# mainboard-mini.net
KiCad netlist of a schematic drawn in EAGLE
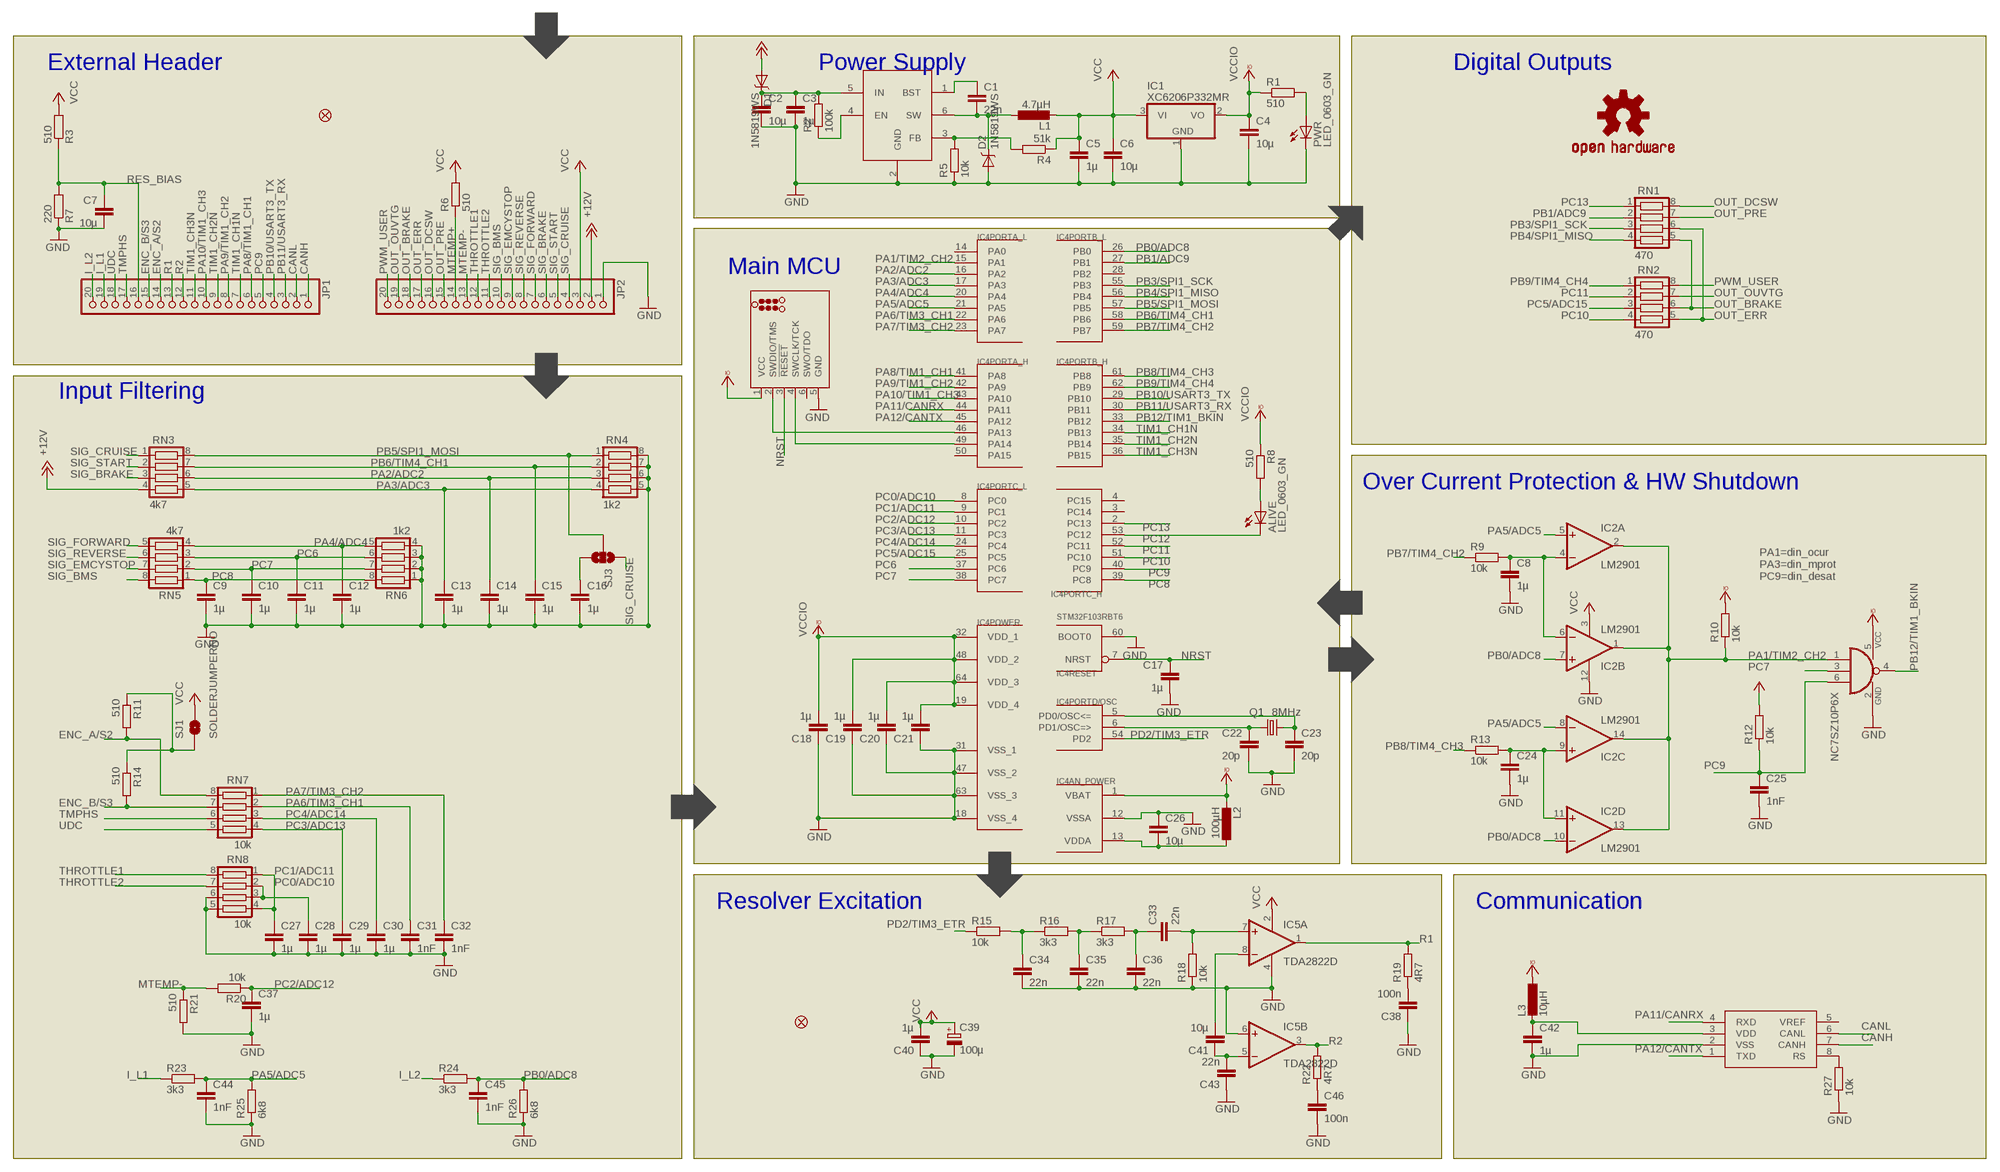
[diagram p0: schematic, sheet 1]

(export (version "E")
  (design (tool "Eeschema 10.0.6"))
  (components
    (comp (ref "ALIVE")
      (value "LED_0603_GN")
      (footprint "eagle-import:SML0805")
      (libsource (lib "eagle-import") (part "LEDSML0805"))
    )
    (comp (ref "C1")
      (value "22n")
      (footprint "eagle-import:C0603")
      (libsource (lib "eagle-import") (part "C-EUC0603"))
    )
    (comp (ref "C2")
      (value "10µ")
      (footprint "eagle-import:C0603")
      (libsource (lib "eagle-import") (part "C-EUC0603"))
    )
    (comp (ref "C3")
      (value "1µ")
      (footprint "eagle-import:C0603")
      (libsource (lib "eagle-import") (part "C-EUC0603"))
    )
    (comp (ref "C4")
      (value "10µ")
      (footprint "eagle-import:C0603")
      (libsource (lib "eagle-import") (part "C-EUC0603"))
    )
    (comp (ref "C5")
      (value "1µ")
      (footprint "eagle-import:C0603")
      (libsource (lib "eagle-import") (part "C-EUC0603"))
    )
    (comp (ref "C6")
      (value "10µ")
      (footprint "eagle-import:C0603")
      (libsource (lib "eagle-import") (part "C-EUC0603"))
    )
    (comp (ref "C7")
      (value "10µ")
      (footprint "eagle-import:C0603")
      (libsource (lib "eagle-import") (part "C-EUC0603"))
    )
    (comp (ref "C8")
      (value "1µ")
      (footprint "eagle-import:C0603")
      (libsource (lib "eagle-import") (part "C-EUC0603"))
    )
    (comp (ref "C9")
      (value "1µ")
      (footprint "eagle-import:C0603")
      (libsource (lib "eagle-import") (part "C-EUC0603"))
    )
    (comp (ref "C10")
      (value "1µ")
      (footprint "eagle-import:C0603")
      (libsource (lib "eagle-import") (part "C-EUC0603"))
    )
    (comp (ref "C11")
      (value "1µ")
      (footprint "eagle-import:C0603")
      (libsource (lib "eagle-import") (part "C-EUC0603"))
    )
    (comp (ref "C12")
      (value "1µ")
      (footprint "eagle-import:C0603")
      (libsource (lib "eagle-import") (part "C-EUC0603"))
    )
    (comp (ref "C13")
      (value "1µ")
      (footprint "eagle-import:C0603")
      (libsource (lib "eagle-import") (part "C-EUC0603"))
    )
    (comp (ref "C14")
      (value "1µ")
      (footprint "eagle-import:C0603")
      (libsource (lib "eagle-import") (part "C-EUC0603"))
    )
    (comp (ref "C15")
      (value "1µ")
      (footprint "eagle-import:C0603")
      (libsource (lib "eagle-import") (part "C-EUC0603"))
    )
    (comp (ref "C16")
      (value "1µ")
      (footprint "eagle-import:C0603")
      (libsource (lib "eagle-import") (part "C-EUC0603"))
    )
    (comp (ref "C17")
      (value "1µ")
      (footprint "eagle-import:C0603")
      (libsource (lib "eagle-import") (part "C-EUC0603"))
    )
    (comp (ref "C18")
      (value "1µ")
      (footprint "eagle-import:C0603")
      (libsource (lib "eagle-import") (part "C-EUC0603"))
    )
    (comp (ref "C19")
      (value "1µ")
      (footprint "eagle-import:C0603")
      (libsource (lib "eagle-import") (part "C-EUC0603"))
    )
    (comp (ref "C20")
      (value "1µ")
      (footprint "eagle-import:C0603")
      (libsource (lib "eagle-import") (part "C-EUC0603"))
    )
    (comp (ref "C21")
      (value "1µ")
      (footprint "eagle-import:C0603")
      (libsource (lib "eagle-import") (part "C-EUC0603"))
    )
    (comp (ref "C22")
      (value "20p")
      (footprint "eagle-import:C0603")
      (libsource (lib "eagle-import") (part "C-EUC0603"))
    )
    (comp (ref "C23")
      (value "20p")
      (footprint "eagle-import:C0603")
      (libsource (lib "eagle-import") (part "C-EUC0603"))
    )
    (comp (ref "C24")
      (value "1µ")
      (footprint "eagle-import:C0603")
      (libsource (lib "eagle-import") (part "C-EUC0603"))
    )
    (comp (ref "C25")
      (value "1nF")
      (footprint "eagle-import:C0603")
      (libsource (lib "eagle-import") (part "C-EUC0603"))
    )
    (comp (ref "C26")
      (value "10µ")
      (footprint "eagle-import:C0603")
      (libsource (lib "eagle-import") (part "C-EUC0603"))
    )
    (comp (ref "C27")
      (value "1µ")
      (footprint "eagle-import:C0603")
      (libsource (lib "eagle-import") (part "C-EUC0603"))
    )
    (comp (ref "C28")
      (value "1µ")
      (footprint "eagle-import:C0603")
      (libsource (lib "eagle-import") (part "C-EUC0603"))
    )
    (comp (ref "C29")
      (value "1µ")
      (footprint "eagle-import:C0603")
      (libsource (lib "eagle-import") (part "C-EUC0603"))
    )
    (comp (ref "C30")
      (value "1µ")
      (footprint "eagle-import:C0603")
      (libsource (lib "eagle-import") (part "C-EUC0603"))
    )
    (comp (ref "C31")
      (value "1nF")
      (footprint "eagle-import:C0603")
      (libsource (lib "eagle-import") (part "C-EUC0603"))
    )
    (comp (ref "C32")
      (value "1nF")
      (footprint "eagle-import:C0603")
      (libsource (lib "eagle-import") (part "C-EUC0603"))
    )
    (comp (ref "C33")
      (value "22n")
      (footprint "eagle-import:C0603")
      (libsource (lib "eagle-import") (part "C-EUC0603"))
    )
    (comp (ref "C34")
      (value "22n")
      (footprint "eagle-import:C0603")
      (libsource (lib "eagle-import") (part "C-EUC0603"))
    )
    (comp (ref "C35")
      (value "22n")
      (footprint "eagle-import:C0603")
      (libsource (lib "eagle-import") (part "C-EUC0603"))
    )
    (comp (ref "C36")
      (value "22n")
      (footprint "eagle-import:C0603")
      (libsource (lib "eagle-import") (part "C-EUC0603"))
    )
    (comp (ref "C37")
      (value "1µ")
      (footprint "eagle-import:C0603")
      (libsource (lib "eagle-import") (part "C-EUC0603"))
    )
    (comp (ref "C38")
      (value "100n")
      (footprint "eagle-import:C0603")
      (libsource (lib "eagle-import") (part "C-EUC0603"))
    )
    (comp (ref "C39")
      (value "100µ")
      (footprint "eagle-import:B_3528-21R")
      (libsource (lib "eagle-import") (part "CPOL-EUB/3528-21R"))
    )
    (comp (ref "C40")
      (value "1µ")
      (footprint "eagle-import:C0603")
      (libsource (lib "eagle-import") (part "C-EUC0603"))
    )
    (comp (ref "C41")
      (value "10µ")
      (footprint "eagle-import:C0603")
      (libsource (lib "eagle-import") (part "C-EUC0603"))
    )
    (comp (ref "C42")
      (value "1µ")
      (footprint "eagle-import:C0603")
      (libsource (lib "eagle-import") (part "C-EUC0603"))
    )
    (comp (ref "C43")
      (value "22n")
      (footprint "eagle-import:C0603")
      (libsource (lib "eagle-import") (part "C-EUC0603"))
    )
    (comp (ref "C44")
      (value "1nF")
      (footprint "eagle-import:C0603")
      (libsource (lib "eagle-import") (part "C-EUC0603"))
    )
    (comp (ref "C45")
      (value "1nF")
      (footprint "eagle-import:C0603")
      (libsource (lib "eagle-import") (part "C-EUC0603"))
    )
    (comp (ref "C46")
      (value "100n")
      (footprint "eagle-import:C0603")
      (libsource (lib "eagle-import") (part "C-EUC0603"))
    )
    (comp (ref "D1")
      (value "1N5819WS")
      (footprint "eagle-import:SOD-323")
      (libsource (lib "eagle-import") (part "BAT20JFILM"))
    )
    (comp (ref "D2")
      (value "1N5819WS")
      (footprint "eagle-import:SOD-323")
      (libsource (lib "eagle-import") (part "BAT20JFILM"))
    )
    (comp (ref "FID1")
      (value "FIDUCIAL1X2.5")
      (footprint "eagle-import:FIDUCIAL-1X2.5")
      (libsource (lib "eagle-import") (part "FIDUCIAL1X2.5"))
    )
    (comp (ref "FID2")
      (value "FIDUCIAL1X2.5")
      (footprint "eagle-import:FIDUCIAL-1X2.5")
      (libsource (lib "eagle-import") (part "FIDUCIAL1X2.5"))
    )
    (comp (ref "IC1")
      (value "XC6206P332MR")
      (footprint "eagle-import:SOT23")
      (libsource (lib "eagle-import") (part "MCP1703CB"))
    )
    (comp (ref "IC2")
      (value "LM2901")
      (footprint "eagle-import:SO14")
      (libsource (lib "eagle-import") (part "LM339D"))
    )
    (comp (ref "IC3")
      (value "NC7SZ10P6X")
      (footprint "eagle-import:SC70-6")
      (libsource (lib "eagle-import") (part "741G10X"))
    )
    (comp (ref "IC4")
      (value "STM32F103RBT6")
      (footprint "eagle-import:TQFP64")
      (libsource (lib "eagle-import") (part "STM32F10XRXT6"))
    )
    (comp (ref "IC5")
      (value "TDA2822D")
      (footprint "eagle-import:SO08")
      (libsource (lib "eagle-import") (part "TDA2822D"))
    )
    (comp (ref "IC6")
      (value "SN65HVD230")
      (footprint "eagle-import:SO08")
      (libsource (lib "eagle-import") (part "MCP2551"))
    )
    (comp (ref "IC7")
      (value "RT8259GE")
      (footprint "eagle-import:SOT23-6")
      (libsource (lib "eagle-import") (part "MB2359DJ"))
    )
    (comp (ref "J1")
      (value "TC2030_SWD-MCP")
      (footprint "eagle-import:TC2030-MCP")
      (libsource (lib "eagle-import") (part "TC2030_SWD-MCP"))
    )
    (comp (ref "JP1")
      (value "PINHD-1X20")
      (footprint "eagle-import:1X20")
      (libsource (lib "eagle-import") (part "PINHD-1X20"))
    )
    (comp (ref "JP2")
      (value "PINHD-1X20")
      (footprint "eagle-import:1X20")
      (libsource (lib "eagle-import") (part "PINHD-1X20"))
    )
    (comp (ref "L1")
      (value "4.7µH")
      (footprint "eagle-import:L2825P")
      (libsource (lib "eagle-import") (part "L-EUL2825P"))
    )
    (comp (ref "L2")
      (value "100µH")
      (footprint "eagle-import:L2012C")
      (libsource (lib "eagle-import") (part "L-EUL2012C"))
    )
    (comp (ref "L3")
      (value "10µH")
      (footprint "eagle-import:L2012C")
      (libsource (lib "eagle-import") (part "L-EUL2012C"))
    )
    (comp (ref "LOGO1")
      (value "OSHW-LOGOM")
      (footprint "eagle-import:OSHW-LOGO-M")
      (libsource (lib "eagle-import") (part "OSHW-LOGOM"))
    )
    (comp (ref "PWR")
      (value "LED_0603_GN")
      (footprint "eagle-import:SML0805")
      (libsource (lib "eagle-import") (part "LEDSML0805"))
    )
    (comp (ref "Q1")
      (value "8MHz")
      (footprint "eagle-import:CRYSTAL-TXC-7A")
      (libsource (lib "eagle-import") (part "CRYSTALTXC-7A"))
    )
    (comp (ref "R1")
      (value "510")
      (footprint "eagle-import:R0603")
      (libsource (lib "eagle-import") (part "R-EU_R0603"))
    )
    (comp (ref "R2")
      (value "100k")
      (footprint "eagle-import:R0603")
      (libsource (lib "eagle-import") (part "R-EU_R0603"))
    )
    (comp (ref "R3")
      (value "510")
      (footprint "eagle-import:R0603")
      (libsource (lib "eagle-import") (part "R-EU_R0603"))
    )
    (comp (ref "R4")
      (value "51k")
      (footprint "eagle-import:R0603")
      (libsource (lib "eagle-import") (part "R-EU_R0603"))
    )
    (comp (ref "R5")
      (value "10k")
      (footprint "eagle-import:R0603")
      (libsource (lib "eagle-import") (part "R-EU_R0603"))
    )
    (comp (ref "R6")
      (value "510")
      (footprint "eagle-import:R0603")
      (libsource (lib "eagle-import") (part "R-EU_R0603"))
    )
    (comp (ref "R7")
      (value "220")
      (footprint "eagle-import:R0603")
      (libsource (lib "eagle-import") (part "R-EU_R0603"))
    )
    (comp (ref "R8")
      (value "510")
      (footprint "eagle-import:R0603")
      (libsource (lib "eagle-import") (part "R-EU_R0603"))
    )
    (comp (ref "R9")
      (value "10k")
      (footprint "eagle-import:R0603")
      (libsource (lib "eagle-import") (part "R-EU_R0603"))
    )
    (comp (ref "R10")
      (value "10k")
      (footprint "eagle-import:R0603")
      (libsource (lib "eagle-import") (part "R-EU_R0603"))
    )
    (comp (ref "R11")
      (value "510")
      (footprint "eagle-import:R0603")
      (libsource (lib "eagle-import") (part "R-EU_R0603"))
    )
    (comp (ref "R12")
      (value "10k")
      (footprint "eagle-import:R0603")
      (libsource (lib "eagle-import") (part "R-EU_R0603"))
    )
    (comp (ref "R13")
      (value "10k")
      (footprint "eagle-import:R0603")
      (libsource (lib "eagle-import") (part "R-EU_R0603"))
    )
    (comp (ref "R14")
      (value "510")
      (footprint "eagle-import:R0603")
      (libsource (lib "eagle-import") (part "R-EU_R0603"))
    )
    (comp (ref "R15")
      (value "10k")
      (footprint "eagle-import:R0603")
      (libsource (lib "eagle-import") (part "R-EU_R0603"))
    )
    (comp (ref "R16")
      (value "3k3")
      (footprint "eagle-import:R0603")
      (libsource (lib "eagle-import") (part "R-EU_R0603"))
    )
    (comp (ref "R17")
      (value "3k3")
      (footprint "eagle-import:R0603")
      (libsource (lib "eagle-import") (part "R-EU_R0603"))
    )
    (comp (ref "R18")
      (value "10k")
      (footprint "eagle-import:R0603")
      (libsource (lib "eagle-import") (part "R-EU_R0603"))
    )
    (comp (ref "R19")
      (value "4R7")
      (footprint "eagle-import:R0603")
      (libsource (lib "eagle-import") (part "R-EU_R0603"))
    )
    (comp (ref "R20")
      (value "10k")
      (footprint "eagle-import:R0603")
      (libsource (lib "eagle-import") (part "R-EU_R0603"))
    )
    (comp (ref "R21")
      (value "510")
      (footprint "eagle-import:R0603")
      (libsource (lib "eagle-import") (part "R-EU_R0603"))
    )
    (comp (ref "R22")
      (value "4R7")
      (footprint "eagle-import:R0603")
      (libsource (lib "eagle-import") (part "R-EU_R0603"))
    )
    (comp (ref "R23")
      (value "3k3")
      (footprint "eagle-import:R0603")
      (libsource (lib "eagle-import") (part "R-EU_R0603"))
    )
    (comp (ref "R24")
      (value "3k3")
      (footprint "eagle-import:R0603")
      (libsource (lib "eagle-import") (part "R-EU_R0603"))
    )
    (comp (ref "R25")
      (value "6k8")
      (footprint "eagle-import:R0603")
      (libsource (lib "eagle-import") (part "R-EU_R0603"))
    )
    (comp (ref "R26")
      (value "6k8")
      (footprint "eagle-import:R0603")
      (libsource (lib "eagle-import") (part "R-EU_R0603"))
    )
    (comp (ref "R27")
      (value "10k")
      (footprint "eagle-import:R0603")
      (libsource (lib "eagle-import") (part "R-EU_R0603"))
    )
    (comp (ref "RN1")
      (value "470")
      (footprint "eagle-import:CTS742C083")
      (libsource (lib "eagle-import") (part "CTS742C083"))
    )
    (comp (ref "RN2")
      (value "470")
      (footprint "eagle-import:CTS742C083")
      (libsource (lib "eagle-import") (part "CTS742C083"))
    )
    (comp (ref "RN3")
      (value "4k7")
      (footprint "eagle-import:CTS742C083")
      (libsource (lib "eagle-import") (part "CTS742C083"))
    )
    (comp (ref "RN4")
      (value "1k2")
      (footprint "eagle-import:CTS742C083")
      (libsource (lib "eagle-import") (part "CTS742C083"))
    )
    (comp (ref "RN5")
      (value "4k7")
      (footprint "eagle-import:CTS742C083")
      (libsource (lib "eagle-import") (part "CTS742C083"))
    )
    (comp (ref "RN6")
      (value "1k2")
      (footprint "eagle-import:CTS742C083")
      (libsource (lib "eagle-import") (part "CTS742C083"))
    )
    (comp (ref "RN7")
      (value "10k")
      (footprint "eagle-import:CTS742C083")
      (libsource (lib "eagle-import") (part "CTS742C083"))
    )
    (comp (ref "RN8")
      (value "10k")
      (footprint "eagle-import:CTS742C083")
      (libsource (lib "eagle-import") (part "CTS742C083"))
    )
    (comp (ref "SJ1")
      (value "SOLDERJUMPERNO")
      (footprint "eagle-import:SJ_2S-NO")
      (libsource (lib "eagle-import") (part "SOLDERJUMPERNO"))
    )
    (comp (ref "SJ3")
      (value "SOLDERJUMPER_2WAYPASTE2&3")
      (footprint "eagle-import:SJ_3_PASTE2&3")
      (libsource (lib "eagle-import") (part "SOLDERJUMPER_2WAYPASTE2&3"))
    )
  )
  (nets
    (net (code "1") (name "+12V") (class "Default")
      (node (ref "D1") (pin "2") (pinfunction "A_2") (pintype "passive"))
      (node (ref "JP2") (pin "2") (pinfunction "2_2") (pintype "passive"))
      (node (ref "RN3") (pin "4") (pinfunction "4_4") (pintype "passive"))
    )
    (net (code "2") (name "/CANH") (class "Default")
      (node (ref "IC6") (pin "7") (pinfunction "CANH_7") (pintype "bidirectional"))
      (node (ref "JP1") (pin "1") (pinfunction "1_1") (pintype "passive"))
    )
    (net (code "3") (name "/CANL") (class "Default")
      (node (ref "IC6") (pin "6") (pinfunction "CANL_6") (pintype "bidirectional"))
      (node (ref "JP1") (pin "2") (pinfunction "2_2") (pintype "passive"))
    )
    (net (code "4") (name "/ENC_A{slash}S2") (class "Default")
      (node (ref "JP1") (pin "14") (pinfunction "14_14") (pintype "passive"))
      (node (ref "R11") (pin "2") (pinfunction "2_2") (pintype "passive"))
      (node (ref "RN7") (pin "8") (pinfunction "8_8") (pintype "passive"))
    )
    (net (code "5") (name "/ENC_B{slash}S3") (class "Default")
      (node (ref "JP1") (pin "15") (pinfunction "15_15") (pintype "passive"))
      (node (ref "R14") (pin "2") (pinfunction "2_2") (pintype "passive"))
      (node (ref "RN7") (pin "7") (pinfunction "7_7") (pintype "passive"))
    )
    (net (code "6") (name "/I_L1") (class "Default")
      (node (ref "JP1") (pin "19") (pinfunction "19_19") (pintype "passive"))
      (node (ref "R23") (pin "1") (pinfunction "1_1") (pintype "passive"))
    )
    (net (code "7") (name "/I_L2") (class "Default")
      (node (ref "JP1") (pin "20") (pinfunction "20_20") (pintype "passive"))
      (node (ref "R24") (pin "1") (pinfunction "1_1") (pintype "passive"))
    )
    (net (code "8") (name "/MTEMP+") (class "Default")
      (node (ref "JP2") (pin "14") (pinfunction "14_14") (pintype "passive"))
      (node (ref "R6") (pin "1") (pinfunction "1_1") (pintype "passive"))
    )
    (net (code "9") (name "/MTEMP-") (class "Default")
      (node (ref "JP2") (pin "13") (pinfunction "13_13") (pintype "passive"))
      (node (ref "R20") (pin "2") (pinfunction "2_2") (pintype "passive"))
      (node (ref "R21") (pin "1") (pinfunction "1_1") (pintype "passive"))
    )
    (net (code "10") (name "/NRST") (class "Default")
      (node (ref "C17") (pin "1") (pinfunction "1_1") (pintype "passive"))
      (node (ref "IC4") (pin "7") (pinfunction "NRST_7") (pintype "input"))
      (node (ref "J1") (pin "3") (pinfunction "~{RESET}_3") (pintype "output"))
    )
    (net (code "11") (name "/OUT_BRAKE") (class "Default")
      (node (ref "JP2") (pin "18") (pinfunction "18_18") (pintype "passive"))
      (node (ref "RN1") (pin "5") (pinfunction "5_5") (pintype "passive"))
      (node (ref "RN2") (pin "6") (pinfunction "6_6") (pintype "passive"))
    )
    (net (code "12") (name "/OUT_DCSW") (class "Default")
      (node (ref "JP2") (pin "16") (pinfunction "16_16") (pintype "passive"))
      (node (ref "RN1") (pin "8") (pinfunction "8_8") (pintype "passive"))
    )
    (net (code "13") (name "/OUT_ERR") (class "Default")
      (node (ref "JP2") (pin "17") (pinfunction "17_17") (pintype "passive"))
      (node (ref "RN1") (pin "6") (pinfunction "6_6") (pintype "passive"))
      (node (ref "RN2") (pin "5") (pinfunction "5_5") (pintype "passive"))
    )
    (net (code "14") (name "/OUT_OUVTG") (class "Default")
      (node (ref "JP2") (pin "19") (pinfunction "19_19") (pintype "passive"))
      (node (ref "RN2") (pin "7") (pinfunction "7_7") (pintype "passive"))
    )
    (net (code "15") (name "/OUT_PRE") (class "Default")
      (node (ref "JP2") (pin "15") (pinfunction "15_15") (pintype "passive"))
      (node (ref "RN1") (pin "7") (pinfunction "7_7") (pintype "passive"))
    )
    (net (code "16") (name "/PA1{slash}TIM2_CH2") (class "Default")
      (node (ref "IC2") (pin "1") (pinfunction "OUT_1") (pintype "open_collector"))
      (node (ref "IC2") (pin "13") (pinfunction "OUT_13") (pintype "open_collector"))
      (node (ref "IC2") (pin "14") (pinfunction "OUT_14") (pintype "open_collector"))
      (node (ref "IC2") (pin "2") (pinfunction "OUT_2") (pintype "open_collector"))
      (node (ref "IC3") (pin "1") (pinfunction "I0_1") (pintype "input"))
      (node (ref "IC4") (pin "15") (pinfunction "PA1_15") (pintype "bidirectional"))
      (node (ref "R10") (pin "1") (pinfunction "1_1") (pintype "passive"))
    )
    (net (code "17") (name "/PA2{slash}ADC2") (class "Default")
      (node (ref "C14") (pin "1") (pinfunction "1_1") (pintype "passive"))
      (node (ref "IC4") (pin "16") (pinfunction "PA2_16") (pintype "bidirectional"))
      (node (ref "RN3") (pin "6") (pinfunction "6_6") (pintype "passive"))
      (node (ref "RN4") (pin "3") (pinfunction "3_3") (pintype "passive"))
    )
    (net (code "18") (name "/PA3{slash}ADC3") (class "Default")
      (node (ref "C13") (pin "1") (pinfunction "1_1") (pintype "passive"))
      (node (ref "IC4") (pin "17") (pinfunction "PA3_17") (pintype "bidirectional"))
      (node (ref "RN3") (pin "5") (pinfunction "5_5") (pintype "passive"))
      (node (ref "RN4") (pin "4") (pinfunction "4_4") (pintype "passive"))
    )
    (net (code "19") (name "/PA4{slash}ADC4") (class "Default")
      (node (ref "C12") (pin "1") (pinfunction "1_1") (pintype "passive"))
      (node (ref "IC4") (pin "20") (pinfunction "PA4_20") (pintype "bidirectional"))
      (node (ref "RN5") (pin "4") (pinfunction "4_4") (pintype "passive"))
      (node (ref "RN6") (pin "5") (pinfunction "5_5") (pintype "passive"))
    )
    (net (code "20") (name "/PA5{slash}ADC5") (class "Default")
      (node (ref "C44") (pin "1") (pinfunction "1_1") (pintype "passive"))
      (node (ref "IC2") (pin "5") (pinfunction "+IN_5") (pintype "input"))
      (node (ref "IC2") (pin "8") (pinfunction "-IN_8") (pintype "input"))
      (node (ref "IC4") (pin "21") (pinfunction "PA5_21") (pintype "bidirectional"))
      (node (ref "R23") (pin "2") (pinfunction "2_2") (pintype "passive"))
      (node (ref "R25") (pin "2") (pinfunction "2_2") (pintype "passive"))
    )
    (net (code "21") (name "/PA6{slash}TIM3_CH1") (class "Default")
      (node (ref "C31") (pin "1") (pinfunction "1_1") (pintype "passive"))
      (node (ref "IC4") (pin "22") (pinfunction "PA6_22") (pintype "bidirectional"))
      (node (ref "RN7") (pin "2") (pinfunction "2_2") (pintype "passive"))
    )
    (net (code "22") (name "/PA7{slash}TIM3_CH2") (class "Default")
      (node (ref "C32") (pin "1") (pinfunction "1_1") (pintype "passive"))
      (node (ref "IC4") (pin "23") (pinfunction "PA7_23") (pintype "bidirectional"))
      (node (ref "RN7") (pin "1") (pinfunction "1_1") (pintype "passive"))
    )
    (net (code "23") (name "/PA8{slash}TIM1_CH1") (class "Default")
      (node (ref "IC4") (pin "41") (pinfunction "PA8_41") (pintype "bidirectional"))
      (node (ref "JP1") (pin "6") (pinfunction "6_6") (pintype "passive"))
    )
    (net (code "24") (name "/PA9{slash}TIM1_CH2") (class "Default")
      (node (ref "IC4") (pin "42") (pinfunction "PA9_42") (pintype "bidirectional"))
      (node (ref "JP1") (pin "8") (pinfunction "8_8") (pintype "passive"))
    )
    (net (code "25") (name "/PA10{slash}TIM1_CH3") (class "Default")
      (node (ref "IC4") (pin "43") (pinfunction "PA10_43") (pintype "bidirectional"))
      (node (ref "JP1") (pin "10") (pinfunction "10_10") (pintype "passive"))
    )
    (net (code "26") (name "/PA11{slash}CANRX") (class "Default")
      (node (ref "IC4") (pin "44") (pinfunction "PA11_44") (pintype "bidirectional"))
      (node (ref "IC6") (pin "4") (pinfunction "RXD_4") (pintype "bidirectional"))
    )
    (net (code "27") (name "/PA12{slash}CANTX") (class "Default")
      (node (ref "IC4") (pin "45") (pinfunction "PA12_45") (pintype "bidirectional"))
      (node (ref "IC6") (pin "1") (pinfunction "TXD_1") (pintype "bidirectional"))
    )
    (net (code "28") (name "/PB0{slash}ADC8") (class "Default")
      (node (ref "C45") (pin "1") (pinfunction "1_1") (pintype "passive"))
      (node (ref "IC2") (pin "10") (pinfunction "-IN_10") (pintype "input"))
      (node (ref "IC2") (pin "7") (pinfunction "+IN_7") (pintype "input"))
      (node (ref "IC4") (pin "26") (pinfunction "PB0_26") (pintype "bidirectional"))
      (node (ref "R24") (pin "2") (pinfunction "2_2") (pintype "passive"))
      (node (ref "R26") (pin "2") (pinfunction "2_2") (pintype "passive"))
    )
    (net (code "29") (name "/PB1{slash}ADC9") (class "Default")
      (node (ref "IC4") (pin "27") (pinfunction "PB1_27") (pintype "bidirectional"))
      (node (ref "RN1") (pin "2") (pinfunction "2_2") (pintype "passive"))
    )
    (net (code "30") (name "/PB3{slash}SPI1_SCK") (class "Default")
      (node (ref "IC4") (pin "55") (pinfunction "PB3_55") (pintype "bidirectional"))
      (node (ref "RN1") (pin "3") (pinfunction "3_3") (pintype "passive"))
    )
    (net (code "31") (name "/PB4{slash}SPI1_MISO") (class "Default")
      (node (ref "IC4") (pin "56") (pinfunction "PB4_56") (pintype "bidirectional"))
      (node (ref "RN1") (pin "4") (pinfunction "4_4") (pintype "passive"))
    )
    (net (code "32") (name "/PB5{slash}SPI1_MOSI") (class "Default")
      (node (ref "IC4") (pin "57") (pinfunction "PB5_57") (pintype "bidirectional"))
      (node (ref "RN3") (pin "8") (pinfunction "8_8") (pintype "passive"))
      (node (ref "RN4") (pin "1") (pinfunction "1_1") (pintype "passive"))
      (node (ref "SJ3") (pin "2") (pinfunction "2_2") (pintype "passive"))
    )
    (net (code "33") (name "/PB6{slash}TIM4_CH1") (class "Default")
      (node (ref "C15") (pin "1") (pinfunction "1_1") (pintype "passive"))
      (node (ref "IC4") (pin "58") (pinfunction "PB6_58") (pintype "bidirectional"))
      (node (ref "RN3") (pin "7") (pinfunction "7_7") (pintype "passive"))
      (node (ref "RN4") (pin "2") (pinfunction "2_2") (pintype "passive"))
    )
    (net (code "34") (name "/PB7{slash}TIM4_CH2") (class "Default")
      (node (ref "IC4") (pin "59") (pinfunction "PB7_59") (pintype "bidirectional"))
      (node (ref "R9") (pin "1") (pinfunction "1_1") (pintype "passive"))
    )
    (net (code "35") (name "/PB8{slash}TIM4_CH3") (class "Default")
      (node (ref "IC4") (pin "61") (pinfunction "PB8_61") (pintype "bidirectional"))
      (node (ref "R13") (pin "1") (pinfunction "1_1") (pintype "passive"))
    )
    (net (code "36") (name "/PB9{slash}TIM4_CH4") (class "Default")
      (node (ref "IC4") (pin "62") (pinfunction "PB9_62") (pintype "bidirectional"))
      (node (ref "RN2") (pin "1") (pinfunction "1_1") (pintype "passive"))
    )
    (net (code "37") (name "/PB10{slash}USART3_TX") (class "Default")
      (node (ref "IC4") (pin "29") (pinfunction "PB10_29") (pintype "bidirectional"))
      (node (ref "JP1") (pin "4") (pinfunction "4_4") (pintype "passive"))
    )
    (net (code "38") (name "/PB11{slash}USART3_RX") (class "Default")
      (node (ref "IC4") (pin "30") (pinfunction "PB11_30") (pintype "bidirectional"))
      (node (ref "JP1") (pin "3") (pinfunction "3_3") (pintype "passive"))
    )
    (net (code "39") (name "/PB12{slash}TIM1_BKIN") (class "Default")
      (node (ref "IC3") (pin "4") (pinfunction "O_4") (pintype "open_collector"))
      (node (ref "IC4") (pin "33") (pinfunction "PB12_33") (pintype "bidirectional"))
    )
    (net (code "40") (name "/PC0{slash}ADC10") (class "Default")
      (node (ref "C28") (pin "1") (pinfunction "1_1") (pintype "passive"))
      (node (ref "IC4") (pin "8") (pinfunction "PC0_8") (pintype "bidirectional"))
      (node (ref "RN8") (pin "2") (pinfunction "2_2") (pintype "passive"))
      (node (ref "RN8") (pin "3") (pinfunction "3_3") (pintype "passive"))
    )
    (net (code "41") (name "/PC1{slash}ADC11") (class "Default")
      (node (ref "C27") (pin "1") (pinfunction "1_1") (pintype "passive"))
      (node (ref "IC4") (pin "9") (pinfunction "PC1_9") (pintype "bidirectional"))
      (node (ref "RN8") (pin "1") (pinfunction "1_1") (pintype "passive"))
      (node (ref "RN8") (pin "4") (pinfunction "4_4") (pintype "passive"))
    )
    (net (code "42") (name "/PC2{slash}ADC12") (class "Default")
      (node (ref "C37") (pin "1") (pinfunction "1_1") (pintype "passive"))
      (node (ref "IC4") (pin "10") (pinfunction "PC2_10") (pintype "bidirectional"))
      (node (ref "R20") (pin "1") (pinfunction "1_1") (pintype "passive"))
    )
    (net (code "43") (name "/PC3{slash}ADC13") (class "Default")
      (node (ref "C29") (pin "1") (pinfunction "1_1") (pintype "passive"))
      (node (ref "IC4") (pin "11") (pinfunction "PC3_11") (pintype "bidirectional"))
      (node (ref "RN7") (pin "4") (pinfunction "4_4") (pintype "passive"))
    )
    (net (code "44") (name "/PC4{slash}ADC14") (class "Default")
      (node (ref "C30") (pin "1") (pinfunction "1_1") (pintype "passive"))
      (node (ref "IC4") (pin "24") (pinfunction "PC4_24") (pintype "bidirectional"))
      (node (ref "RN7") (pin "3") (pinfunction "3_3") (pintype "passive"))
    )
    (net (code "45") (name "/PC5{slash}ADC15") (class "Default")
      (node (ref "IC4") (pin "25") (pinfunction "PC5_25") (pintype "bidirectional"))
      (node (ref "RN2") (pin "3") (pinfunction "3_3") (pintype "passive"))
    )
    (net (code "46") (name "/PC6") (class "Default")
      (node (ref "C11") (pin "1") (pinfunction "1_1") (pintype "passive"))
      (node (ref "IC4") (pin "37") (pinfunction "PC6_37") (pintype "bidirectional"))
      (node (ref "RN5") (pin "3") (pinfunction "3_3") (pintype "passive"))
      (node (ref "RN6") (pin "6") (pinfunction "6_6") (pintype "passive"))
    )
    (net (code "47") (name "/PC7") (class "Default")
      (node (ref "C10") (pin "1") (pinfunction "1_1") (pintype "passive"))
      (node (ref "IC3") (pin "3") (pinfunction "I1_3") (pintype "input"))
      (node (ref "IC4") (pin "38") (pinfunction "PC7_38") (pintype "bidirectional"))
      (node (ref "RN5") (pin "2") (pinfunction "2_2") (pintype "passive"))
      (node (ref "RN6") (pin "7") (pinfunction "7_7") (pintype "passive"))
    )
    (net (code "48") (name "/PC8") (class "Default")
      (node (ref "C9") (pin "1") (pinfunction "1_1") (pintype "passive"))
      (node (ref "IC4") (pin "39") (pinfunction "PC8_39") (pintype "bidirectional"))
      (node (ref "RN5") (pin "1") (pinfunction "1_1") (pintype "passive"))
      (node (ref "RN6") (pin "8") (pinfunction "8_8") (pintype "passive"))
    )
    (net (code "49") (name "/PC9") (class "Default")
      (node (ref "C25") (pin "1") (pinfunction "1_1") (pintype "passive"))
      (node (ref "IC3") (pin "6") (pinfunction "I2_6") (pintype "input"))
      (node (ref "IC4") (pin "40") (pinfunction "PC9_40") (pintype "bidirectional"))
      (node (ref "JP1") (pin "5") (pinfunction "5_5") (pintype "passive"))
      (node (ref "R12") (pin "1") (pinfunction "1_1") (pintype "passive"))
    )
    (net (code "50") (name "/PC10") (class "Default")
      (node (ref "IC4") (pin "51") (pinfunction "PC10_51") (pintype "bidirectional"))
      (node (ref "RN2") (pin "4") (pinfunction "4_4") (pintype "passive"))
    )
    (net (code "51") (name "/PC11") (class "Default")
      (node (ref "IC4") (pin "52") (pinfunction "PC11_52") (pintype "bidirectional"))
      (node (ref "RN2") (pin "2") (pinfunction "2_2") (pintype "passive"))
    )
    (net (code "52") (name "/PC12") (class "Default")
      (node (ref "ALIVE") (pin "C") (pinfunction "C_C") (pintype "passive"))
      (node (ref "IC4") (pin "53") (pinfunction "PC12_53") (pintype "bidirectional"))
    )
    (net (code "53") (name "/PC13") (class "Default")
      (node (ref "IC4") (pin "2") (pinfunction "PC13_2") (pintype "bidirectional"))
      (node (ref "RN1") (pin "1") (pinfunction "1_1") (pintype "passive"))
    )
    (net (code "54") (name "/PD2{slash}TIM3_ETR") (class "Default")
      (node (ref "IC4") (pin "54") (pinfunction "PD2_54") (pintype "bidirectional"))
      (node (ref "R15") (pin "1") (pinfunction "1_1") (pintype "passive"))
    )
    (net (code "55") (name "/PWM_USER") (class "Default")
      (node (ref "JP2") (pin "20") (pinfunction "20_20") (pintype "passive"))
      (node (ref "RN2") (pin "8") (pinfunction "8_8") (pintype "passive"))
    )
    (net (code "56") (name "/R1") (class "Default")
      (node (ref "IC5") (pin "1") (pinfunction "OUT_1") (pintype "output"))
      (node (ref "JP1") (pin "13") (pinfunction "13_13") (pintype "passive"))
      (node (ref "R19") (pin "2") (pinfunction "2_2") (pintype "passive"))
    )
    (net (code "57") (name "/R2") (class "Default")
      (node (ref "IC5") (pin "3") (pinfunction "OUT_3") (pintype "output"))
      (node (ref "JP1") (pin "12") (pinfunction "12_12") (pintype "passive"))
      (node (ref "R22") (pin "2") (pinfunction "2_2") (pintype "passive"))
    )
    (net (code "58") (name "/RES_BIAS") (class "Default")
      (node (ref "C7") (pin "1") (pinfunction "1_1") (pintype "passive"))
      (node (ref "JP1") (pin "16") (pinfunction "16_16") (pintype "passive"))
      (node (ref "R3") (pin "1") (pinfunction "1_1") (pintype "passive"))
      (node (ref "R7") (pin "2") (pinfunction "2_2") (pintype "passive"))
    )
    (net (code "59") (name "/SIG_BMS") (class "Default")
      (node (ref "JP2") (pin "10") (pinfunction "10_10") (pintype "passive"))
      (node (ref "RN5") (pin "8") (pinfunction "8_8") (pintype "passive"))
    )
    (net (code "60") (name "/SIG_BRAKE") (class "Default")
      (node (ref "JP2") (pin "6") (pinfunction "6_6") (pintype "passive"))
      (node (ref "RN3") (pin "3") (pinfunction "3_3") (pintype "passive"))
    )
    (net (code "61") (name "/SIG_CRUISE") (class "Default")
      (node (ref "JP2") (pin "4") (pinfunction "4_4") (pintype "passive"))
      (node (ref "RN3") (pin "1") (pinfunction "1_1") (pintype "passive"))
      (node (ref "SJ3") (pin "1") (pinfunction "1_1") (pintype "passive"))
    )
    (net (code "62") (name "/SIG_EMCYSTOP") (class "Default")
      (node (ref "JP2") (pin "9") (pinfunction "9_9") (pintype "passive"))
      (node (ref "RN5") (pin "7") (pinfunction "7_7") (pintype "passive"))
    )
    (net (code "63") (name "/SIG_FORWARD") (class "Default")
      (node (ref "JP2") (pin "7") (pinfunction "7_7") (pintype "passive"))
      (node (ref "RN5") (pin "5") (pinfunction "5_5") (pintype "passive"))
    )
    (net (code "64") (name "/SIG_REVERSE") (class "Default")
      (node (ref "JP2") (pin "8") (pinfunction "8_8") (pintype "passive"))
      (node (ref "RN5") (pin "6") (pinfunction "6_6") (pintype "passive"))
    )
    (net (code "65") (name "/SIG_START") (class "Default")
      (node (ref "JP2") (pin "5") (pinfunction "5_5") (pintype "passive"))
      (node (ref "RN3") (pin "2") (pinfunction "2_2") (pintype "passive"))
    )
    (net (code "66") (name "/THROTTLE1") (class "Default")
      (node (ref "JP2") (pin "12") (pinfunction "12_12") (pintype "passive"))
      (node (ref "RN8") (pin "8") (pinfunction "8_8") (pintype "passive"))
    )
    (net (code "67") (name "/THROTTLE2") (class "Default")
      (node (ref "JP2") (pin "11") (pinfunction "11_11") (pintype "passive"))
      (node (ref "RN8") (pin "7") (pinfunction "7_7") (pintype "passive"))
    )
    (net (code "68") (name "/TIM1_CH1N") (class "Default")
      (node (ref "IC4") (pin "34") (pinfunction "PB13_34") (pintype "bidirectional"))
      (node (ref "JP1") (pin "7") (pinfunction "7_7") (pintype "passive"))
    )
    (net (code "69") (name "/TIM1_CH2N") (class "Default")
      (node (ref "IC4") (pin "35") (pinfunction "PB14_35") (pintype "bidirectional"))
      (node (ref "JP1") (pin "9") (pinfunction "9_9") (pintype "passive"))
    )
    (net (code "70") (name "/TIM1_CH3N") (class "Default")
      (node (ref "IC4") (pin "36") (pinfunction "PB15_36") (pintype "bidirectional"))
      (node (ref "JP1") (pin "11") (pinfunction "11_11") (pintype "passive"))
    )
    (net (code "71") (name "/TMPHS") (class "Default")
      (node (ref "JP1") (pin "17") (pinfunction "17_17") (pintype "passive"))
      (node (ref "RN7") (pin "6") (pinfunction "6_6") (pintype "passive"))
    )
    (net (code "72") (name "/UDC") (class "Default")
      (node (ref "JP1") (pin "18") (pinfunction "18_18") (pintype "passive"))
      (node (ref "RN7") (pin "5") (pinfunction "5_5") (pintype "passive"))
    )
    (net (code "73") (name "GND") (class "Default")
      (node (ref "C10") (pin "2") (pinfunction "2_2") (pintype "passive"))
      (node (ref "C11") (pin "2") (pinfunction "2_2") (pintype "passive"))
      (node (ref "C12") (pin "2") (pinfunction "2_2") (pintype "passive"))
      (node (ref "C13") (pin "2") (pinfunction "2_2") (pintype "passive"))
      (node (ref "C14") (pin "2") (pinfunction "2_2") (pintype "passive"))
      (node (ref "C15") (pin "2") (pinfunction "2_2") (pintype "passive"))
      (node (ref "C16") (pin "2") (pinfunction "2_2") (pintype "passive"))
      (node (ref "C17") (pin "2") (pinfunction "2_2") (pintype "passive"))
      (node (ref "C18") (pin "1") (pinfunction "1_1") (pintype "passive"))
      (node (ref "C19") (pin "1") (pinfunction "1_1") (pintype "passive"))
      (node (ref "C2") (pin "2") (pinfunction "2_2") (pintype "passive"))
      (node (ref "C20") (pin "1") (pinfunction "1_1") (pintype "passive"))
      (node (ref "C21") (pin "1") (pinfunction "1_1") (pintype "passive"))
      (node (ref "C22") (pin "2") (pinfunction "2_2") (pintype "passive"))
      (node (ref "C23") (pin "2") (pinfunction "2_2") (pintype "passive"))
      (node (ref "C24") (pin "2") (pinfunction "2_2") (pintype "passive"))
      (node (ref "C25") (pin "2") (pinfunction "2_2") (pintype "passive"))
      (node (ref "C26") (pin "1") (pinfunction "1_1") (pintype "passive"))
      (node (ref "C27") (pin "2") (pinfunction "2_2") (pintype "passive"))
      (node (ref "C28") (pin "2") (pinfunction "2_2") (pintype "passive"))
      (node (ref "C29") (pin "2") (pinfunction "2_2") (pintype "passive"))
      (node (ref "C3") (pin "2") (pinfunction "2_2") (pintype "passive"))
      (node (ref "C30") (pin "2") (pinfunction "2_2") (pintype "passive"))
      (node (ref "C31") (pin "2") (pinfunction "2_2") (pintype "passive"))
      (node (ref "C32") (pin "2") (pinfunction "2_2") (pintype "passive"))
      (node (ref "C34") (pin "2") (pinfunction "2_2") (pintype "passive"))
      (node (ref "C35") (pin "2") (pinfunction "2_2") (pintype "passive"))
      (node (ref "C36") (pin "2") (pinfunction "2_2") (pintype "passive"))
      (node (ref "C37") (pin "2") (pinfunction "2_2") (pintype "passive"))
      (node (ref "C38") (pin "1") (pinfunction "1_1") (pintype "passive"))
      (node (ref "C39") (pin "-") (pinfunction "-_-") (pintype "passive"))
      (node (ref "C4") (pin "2") (pinfunction "2_2") (pintype "passive"))
      (node (ref "C40") (pin "1") (pinfunction "1_1") (pintype "passive"))
      (node (ref "C42") (pin "2") (pinfunction "2_2") (pintype "passive"))
      (node (ref "C43") (pin "1") (pinfunction "1_1") (pintype "passive"))
      (node (ref "C44") (pin "2") (pinfunction "2_2") (pintype "passive"))
      (node (ref "C45") (pin "2") (pinfunction "2_2") (pintype "passive"))
      (node (ref "C46") (pin "2") (pinfunction "2_2") (pintype "passive"))
      (node (ref "C5") (pin "2") (pinfunction "2_2") (pintype "passive"))
      (node (ref "C6") (pin "2") (pinfunction "2_2") (pintype "passive"))
      (node (ref "C7") (pin "2") (pinfunction "2_2") (pintype "passive"))
      (node (ref "C8") (pin "2") (pinfunction "2_2") (pintype "passive"))
      (node (ref "C9") (pin "2") (pinfunction "2_2") (pintype "passive"))
      (node (ref "D2") (pin "2") (pinfunction "A_2") (pintype "passive"))
      (node (ref "IC1") (pin "1") (pinfunction "GND_1") (pintype "passive"))
      (node (ref "IC2") (pin "12") (pinfunction "GND_12") (pintype "power_in"))
      (node (ref "IC3") (pin "2") (pinfunction "GND_2") (pintype "power_in"))
      (node (ref "IC4") (pin "12") (pinfunction "VSSA_12") (pintype "power_in"))
      (node (ref "IC4") (pin "18") (pinfunction "VSS_4_18") (pintype "power_in"))
      (node (ref "IC4") (pin "31") (pinfunction "VSS_1_31") (pintype "power_in"))
      (node (ref "IC4") (pin "47") (pinfunction "VSS_2_47") (pintype "power_in"))
      (node (ref "IC4") (pin "60") (pinfunction "BOOT0_60") (pintype "input"))
      (node (ref "IC4") (pin "63") (pinfunction "VSS_3_63") (pintype "power_in"))
      (node (ref "IC5") (pin "4") (pinfunction "V-_4") (pintype "power_in"))
      (node (ref "IC5") (pin "6") (pinfunction "+IN_6") (pintype "input"))
      (node (ref "IC6") (pin "2") (pinfunction "VSS_2") (pintype "bidirectional"))
      (node (ref "IC7") (pin "2") (pinfunction "GND_2") (pintype "bidirectional"))
      (node (ref "J1") (pin "5") (pinfunction "GND_5") (pintype "passive"))
      (node (ref "JP2") (pin "1") (pinfunction "1_1") (pintype "passive"))
      (node (ref "PWR") (pin "C") (pinfunction "C_C") (pintype "passive"))
      (node (ref "R18") (pin "1") (pinfunction "1_1") (pintype "passive"))
      (node (ref "R21") (pin "2") (pinfunction "2_2") (pintype "passive"))
      (node (ref "R25") (pin "1") (pinfunction "1_1") (pintype "passive"))
      (node (ref "R26") (pin "1") (pinfunction "1_1") (pintype "passive"))
      (node (ref "R27") (pin "1") (pinfunction "1_1") (pintype "passive"))
      (node (ref "R5") (pin "1") (pinfunction "1_1") (pintype "passive"))
      (node (ref "R7") (pin "1") (pinfunction "1_1") (pintype "passive"))
      (node (ref "RN4") (pin "5") (pinfunction "5_5") (pintype "passive"))
      (node (ref "RN4") (pin "6") (pinfunction "6_6") (pintype "passive"))
      (node (ref "RN4") (pin "7") (pinfunction "7_7") (pintype "passive"))
      (node (ref "RN4") (pin "8") (pinfunction "8_8") (pintype "passive"))
      (node (ref "RN6") (pin "1") (pinfunction "1_1") (pintype "passive"))
      (node (ref "RN6") (pin "2") (pinfunction "2_2") (pintype "passive"))
      (node (ref "RN6") (pin "3") (pinfunction "3_3") (pintype "passive"))
      (node (ref "RN6") (pin "4") (pinfunction "4_4") (pintype "passive"))
      (node (ref "RN8") (pin "5") (pinfunction "5_5") (pintype "passive"))
      (node (ref "RN8") (pin "6") (pinfunction "6_6") (pintype "passive"))
    )
    (net (code "74") (name "Net-(ALIVE-PadA)") (class "Default")
      (node (ref "ALIVE") (pin "A") (pinfunction "A_A") (pintype "passive"))
      (node (ref "R8") (pin "2") (pinfunction "2_2") (pintype "passive"))
    )
    (net (code "75") (name "Net-(C16-Pad1)") (class "Default")
      (node (ref "C16") (pin "1") (pinfunction "1_1") (pintype "passive"))
      (node (ref "SJ3") (pin "3") (pinfunction "3_3") (pintype "passive"))
    )
    (net (code "76") (name "Net-(C33-Pad1)") (class "Default")
      (node (ref "C33") (pin "1") (pinfunction "1_1") (pintype "passive"))
      (node (ref "C36") (pin "1") (pinfunction "1_1") (pintype "passive"))
      (node (ref "R17") (pin "2") (pinfunction "2_2") (pintype "passive"))
    )
    (net (code "77") (name "Net-(C34-Pad1)") (class "Default")
      (node (ref "C34") (pin "1") (pinfunction "1_1") (pintype "passive"))
      (node (ref "R15") (pin "2") (pinfunction "2_2") (pintype "passive"))
      (node (ref "R16") (pin "1") (pinfunction "1_1") (pintype "passive"))
    )
    (net (code "78") (name "Net-(C35-Pad1)") (class "Default")
      (node (ref "C35") (pin "1") (pinfunction "1_1") (pintype "passive"))
      (node (ref "R16") (pin "2") (pinfunction "2_2") (pintype "passive"))
      (node (ref "R17") (pin "1") (pinfunction "1_1") (pintype "passive"))
    )
    (net (code "79") (name "Net-(C38-Pad2)") (class "Default")
      (node (ref "C38") (pin "2") (pinfunction "2_2") (pintype "passive"))
      (node (ref "R19") (pin "1") (pinfunction "1_1") (pintype "passive"))
    )
    (net (code "80") (name "Net-(C46-Pad1)") (class "Default")
      (node (ref "C46") (pin "1") (pinfunction "1_1") (pintype "passive"))
      (node (ref "R22") (pin "1") (pinfunction "1_1") (pintype "passive"))
    )
    (net (code "81") (name "Net-(D1-C)") (class "Default")
      (node (ref "C2") (pin "1") (pinfunction "1_1") (pintype "passive"))
      (node (ref "C3") (pin "1") (pinfunction "1_1") (pintype "passive"))
      (node (ref "D1") (pin "1") (pinfunction "C_1") (pintype "passive"))
      (node (ref "IC7") (pin "5") (pinfunction "IN_5") (pintype "bidirectional"))
      (node (ref "R2") (pin "2") (pinfunction "2_2") (pintype "passive"))
    )
    (net (code "82") (name "Net-(D2-C)") (class "Default")
      (node (ref "C1") (pin "2") (pinfunction "2_2") (pintype "passive"))
      (node (ref "D2") (pin "1") (pinfunction "C_1") (pintype "passive"))
      (node (ref "IC7") (pin "6") (pinfunction "SW_6") (pintype "bidirectional"))
      (node (ref "L1") (pin "1") (pinfunction "1_1") (pintype "passive"))
    )
    (net (code "83") (name "Net-(IC2A--IN)") (class "Default")
      (node (ref "C8") (pin "1") (pinfunction "1_1") (pintype "passive"))
      (node (ref "IC2") (pin "4") (pinfunction "-IN_4") (pintype "input"))
      (node (ref "IC2") (pin "6") (pinfunction "-IN_6") (pintype "input"))
      (node (ref "R9") (pin "2") (pinfunction "2_2") (pintype "passive"))
    )
    (net (code "84") (name "Net-(IC2C-+IN)") (class "Default")
      (node (ref "C24") (pin "1") (pinfunction "1_1") (pintype "passive"))
      (node (ref "IC2") (pin "11") (pinfunction "+IN_11") (pintype "input"))
      (node (ref "IC2") (pin "9") (pinfunction "+IN_9") (pintype "input"))
      (node (ref "R13") (pin "2") (pinfunction "2_2") (pintype "passive"))
    )
    (net (code "85") (name "Net-(IC4A-VDDA)") (class "Default")
      (node (ref "C26") (pin "2") (pinfunction "2_2") (pintype "passive"))
      (node (ref "IC4") (pin "13") (pinfunction "VDDA_13") (pintype "power_in"))
      (node (ref "L2") (pin "1") (pinfunction "1_1") (pintype "passive"))
    )
    (net (code "86") (name "Net-(IC4B-PA13)") (class "Default")
      (node (ref "IC4") (pin "46") (pinfunction "PA13_46") (pintype "bidirectional"))
      (node (ref "J1") (pin "2") (pinfunction "SWDIO/TMS_2") (pintype "bidirectional"))
    )
    (net (code "87") (name "Net-(IC4B-PA14)") (class "Default")
      (node (ref "IC4") (pin "49") (pinfunction "PA14_49") (pintype "bidirectional"))
      (node (ref "J1") (pin "4") (pinfunction "SWCLK/TCK_4") (pintype "output"))
    )
    (net (code "88") (name "Net-(IC4H-PD0{slash}OSC<=)") (class "Default")
      (node (ref "C23") (pin "1") (pinfunction "1_1") (pintype "passive"))
      (node (ref "IC4") (pin "5") (pinfunction "PD0/OSC<=_5") (pintype "bidirectional"))
      (node (ref "Q1") (pin "P$2") (pinfunction "2_P$2") (pintype "passive"))
    )
    (net (code "89") (name "Net-(IC4H-PD1{slash}OSC=>)") (class "Default")
      (node (ref "C22") (pin "1") (pinfunction "1_1") (pintype "passive"))
      (node (ref "IC4") (pin "6") (pinfunction "PD1/OSC=>_6") (pintype "bidirectional"))
      (node (ref "Q1") (pin "P$1") (pinfunction "1_P$1") (pintype "passive"))
    )
    (net (code "90") (name "Net-(IC5A-+IN)") (class "Default")
      (node (ref "C33") (pin "2") (pinfunction "2_2") (pintype "passive"))
      (node (ref "IC5") (pin "7") (pinfunction "+IN_7") (pintype "input"))
      (node (ref "R18") (pin "2") (pinfunction "2_2") (pintype "passive"))
    )
    (net (code "91") (name "Net-(IC5A--IN)") (class "Default")
      (node (ref "C41") (pin "2") (pinfunction "2_2") (pintype "passive"))
      (node (ref "IC5") (pin "8") (pinfunction "-IN_8") (pintype "input"))
    )
    (net (code "92") (name "Net-(IC5B--IN)") (class "Default")
      (node (ref "C41") (pin "1") (pinfunction "1_1") (pintype "passive"))
      (node (ref "C43") (pin "2") (pinfunction "2_2") (pintype "passive"))
      (node (ref "IC5") (pin "5") (pinfunction "-IN_5") (pintype "input"))
    )
    (net (code "93") (name "Net-(IC6-RS)") (class "Default")
      (node (ref "IC6") (pin "8") (pinfunction "RS_8") (pintype "bidirectional"))
      (node (ref "R27") (pin "2") (pinfunction "2_2") (pintype "passive"))
    )
    (net (code "94") (name "Net-(IC6-VDD)") (class "Default")
      (node (ref "C42") (pin "1") (pinfunction "1_1") (pintype "passive"))
      (node (ref "IC6") (pin "3") (pinfunction "VDD_3") (pintype "bidirectional"))
      (node (ref "L3") (pin "2") (pinfunction "2_2") (pintype "passive"))
    )
    (net (code "95") (name "Net-(IC7-BST)") (class "Default")
      (node (ref "C1") (pin "1") (pinfunction "1_1") (pintype "passive"))
      (node (ref "IC7") (pin "1") (pinfunction "BST_1") (pintype "bidirectional"))
    )
    (net (code "96") (name "Net-(IC7-EN)") (class "Default")
      (node (ref "IC7") (pin "4") (pinfunction "EN_4") (pintype "bidirectional"))
      (node (ref "R2") (pin "1") (pinfunction "1_1") (pintype "passive"))
    )
    (net (code "97") (name "Net-(IC7-FB)") (class "Default")
      (node (ref "IC7") (pin "3") (pinfunction "FB_3") (pintype "bidirectional"))
      (node (ref "R4") (pin "2") (pinfunction "2_2") (pintype "passive"))
      (node (ref "R5") (pin "2") (pinfunction "2_2") (pintype "passive"))
    )
    (net (code "98") (name "Net-(PWR-PadA)") (class "Default")
      (node (ref "PWR") (pin "A") (pinfunction "A_A") (pintype "passive"))
      (node (ref "R1") (pin "2") (pinfunction "2_2") (pintype "passive"))
    )
    (net (code "99") (name "Net-(R11-Pad1)") (class "Default")
      (node (ref "R11") (pin "1") (pinfunction "1_1") (pintype "passive"))
      (node (ref "R14") (pin "1") (pinfunction "1_1") (pintype "passive"))
      (node (ref "SJ1") (pin "1") (pinfunction "1_1") (pintype "passive"))
    )
    (net (code "100") (name "VCC") (class "Default")
      (node (ref "C39") (pin "+") (pinfunction "+_+") (pintype "passive"))
      (node (ref "C40") (pin "2") (pinfunction "2_2") (pintype "passive"))
      (node (ref "C5") (pin "1") (pinfunction "1_1") (pintype "passive"))
      (node (ref "C6") (pin "1") (pinfunction "1_1") (pintype "passive"))
      (node (ref "IC1") (pin "3") (pinfunction "VI_3") (pintype "input"))
      (node (ref "IC2") (pin "3") (pinfunction "V+_3") (pintype "power_in"))
      (node (ref "IC5") (pin "2") (pinfunction "V+_2") (pintype "power_in"))
      (node (ref "JP2") (pin "3") (pinfunction "3_3") (pintype "passive"))
      (node (ref "L1") (pin "2") (pinfunction "2_2") (pintype "passive"))
      (node (ref "R12") (pin "2") (pinfunction "2_2") (pintype "passive"))
      (node (ref "R3") (pin "2") (pinfunction "2_2") (pintype "passive"))
      (node (ref "R4") (pin "1") (pinfunction "1_1") (pintype "passive"))
      (node (ref "R6") (pin "2") (pinfunction "2_2") (pintype "passive"))
      (node (ref "SJ1") (pin "2") (pinfunction "2_2") (pintype "passive"))
    )
    (net (code "101") (name "VCCIO") (class "Default")
      (node (ref "C18") (pin "2") (pinfunction "2_2") (pintype "passive"))
      (node (ref "C19") (pin "2") (pinfunction "2_2") (pintype "passive"))
      (node (ref "C20") (pin "2") (pinfunction "2_2") (pintype "passive"))
      (node (ref "C21") (pin "2") (pinfunction "2_2") (pintype "passive"))
      (node (ref "C4") (pin "1") (pinfunction "1_1") (pintype "passive"))
      (node (ref "IC1") (pin "2") (pinfunction "VO_2") (pintype "passive"))
      (node (ref "IC3") (pin "5") (pinfunction "VCC_5") (pintype "power_in"))
      (node (ref "IC4") (pin "1") (pinfunction "VBAT_1") (pintype "power_in"))
      (node (ref "IC4") (pin "19") (pinfunction "VDD_4_19") (pintype "power_in"))
      (node (ref "IC4") (pin "32") (pinfunction "VDD_1_32") (pintype "power_in"))
      (node (ref "IC4") (pin "48") (pinfunction "VDD_2_48") (pintype "power_in"))
      (node (ref "IC4") (pin "64") (pinfunction "VDD_3_64") (pintype "power_in"))
      (node (ref "J1") (pin "1") (pinfunction "VCC_1") (pintype "passive"))
      (node (ref "L2") (pin "2") (pinfunction "2_2") (pintype "passive"))
      (node (ref "L3") (pin "1") (pinfunction "1_1") (pintype "passive"))
      (node (ref "R1") (pin "1") (pinfunction "1_1") (pintype "passive"))
      (node (ref "R10") (pin "2") (pinfunction "2_2") (pintype "passive"))
      (node (ref "R8") (pin "1") (pinfunction "1_1") (pintype "passive"))
    )
    (net (code "102") (name "unconnected-(IC4B-PA15-Pad50)") (class "Default")
      (node (ref "IC4") (pin "50") (pinfunction "PA15_50") (pintype "bidirectional"))
    )
    (net (code "103") (name "unconnected-(IC4C-PA0-Pad14)") (class "Default")
      (node (ref "IC4") (pin "14") (pinfunction "PA0_14") (pintype "bidirectional"))
    )
    (net (code "104") (name "unconnected-(IC4E-PB2-Pad28)") (class "Default")
      (node (ref "IC4") (pin "28") (pinfunction "PB2_28") (pintype "bidirectional"))
    )
    (net (code "105") (name "unconnected-(IC4F-PC14-Pad3)") (class "Default")
      (node (ref "IC4") (pin "3") (pinfunction "PC14_3") (pintype "bidirectional"))
    )
    (net (code "106") (name "unconnected-(IC4F-PC15-Pad4)") (class "Default")
      (node (ref "IC4") (pin "4") (pinfunction "PC15_4") (pintype "bidirectional"))
    )
    (net (code "107") (name "unconnected-(IC6-VREF-Pad5)") (class "Default")
      (node (ref "IC6") (pin "5") (pinfunction "VREF_5") (pintype "bidirectional"))
    )
    (net (code "108") (name "unconnected-(J1-SWO{slash}TDO-Pad6)") (class "Default")
      (node (ref "J1") (pin "6") (pinfunction "SWO/TDO_6") (pintype "bidirectional"))
    )
  )
)
